# rpi.net
KiCad netlist of a schematic drawn in EAGLE
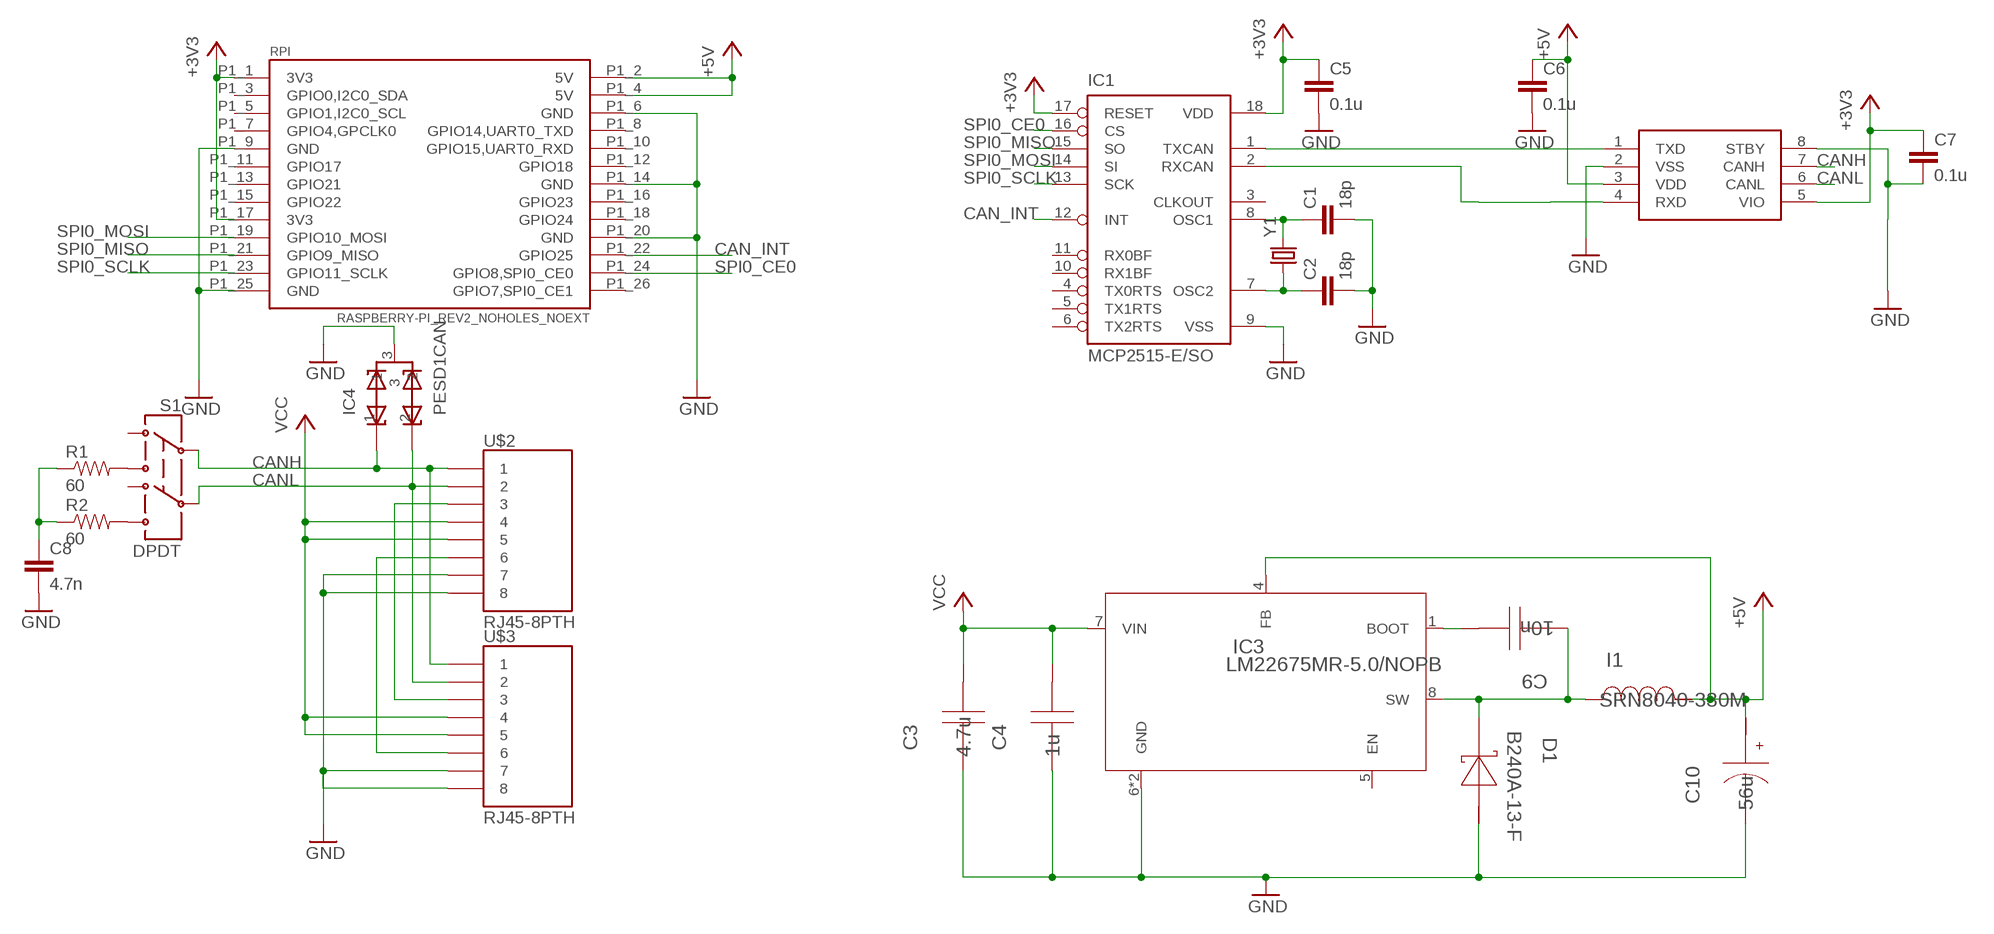
[diagram p0: schematic, sheet 1]

(export (version "E")
  (design (tool "Eeschema 10.0.6"))
  (components
    (comp (ref "C1")
      (value "18p")
      (footprint "eagle-import:0603-CAP")
      (libsource (lib "eagle-import") (part "CAP0603-CAP"))
    )
    (comp (ref "C2")
      (value "18p")
      (footprint "eagle-import:0603-CAP")
      (libsource (lib "eagle-import") (part "CAP0603-CAP"))
    )
    (comp (ref "C3")
      (value "4.7u")
      (footprint "eagle-import:1206")
      (fields (field (name "MANUFACTURER_PART_NUMBER") "GRM31CR71H475KA12L"))
      (libsource (lib "eagle-import") (part "GRM31CR71H475KA12L"))
    )
    (comp (ref "C4")
      (value "1u")
      (footprint "eagle-import:0805")
      (fields (field (name "MANUFACTURER_PART_NUMBER") "GMK212B7105KG-T"))
      (libsource (lib "eagle-import") (part "GMK212B7105KG-T"))
    )
    (comp (ref "C5")
      (value "0.1u")
      (footprint "eagle-import:0603-CAP")
      (libsource (lib "eagle-import") (part "SparkFun-Passives_CAP0603-CAP"))
    )
    (comp (ref "C6")
      (value "0.1u")
      (footprint "eagle-import:0603-CAP")
      (libsource (lib "eagle-import") (part "SparkFun-Passives_CAP0603-CAP"))
    )
    (comp (ref "C7")
      (value "0.1u")
      (footprint "eagle-import:0603-CAP")
      (libsource (lib "eagle-import") (part "SparkFun-Passives_CAP0603-CAP"))
    )
    (comp (ref "C8")
      (value "4.7n")
      (footprint "eagle-import:0603-CAP")
      (libsource (lib "eagle-import") (part "SparkFun-Passives_CAP0603-CAP"))
    )
    (comp (ref "C9")
      (value "10n")
      (footprint "eagle-import:0805")
      (fields (field (name "MANUFACTURER_PART_NUMBER") "C0805C103K5RACTU"))
      (libsource (lib "eagle-import") (part "C0805C103K5RACTU"))
    )
    (comp (ref "C10")
      (value "56u")
      (footprint "eagle-import:SM_RADIAL_6.3AMM")
      (fields (field (name "MANUFACTURER_PART_NUMBER") "10SVP56M"))
      (libsource (lib "eagle-import") (part "10SVP56M"))
    )
    (comp (ref "D1")
      (value "B240A-13-F")
      (footprint "eagle-import:SMA")
      (libsource (lib "eagle-import") (part "B240A-13-F"))
    )
    (comp (ref "I1")
      (value "SRN8040-330M")
      (footprint "eagle-import:SRN8040")
      (libsource (lib "eagle-import") (part "SRN8040-330M"))
    )
    (comp (ref "IC1")
      (value "MCP2515-E/SO")
      (footprint "eagle-import:SO18L")
      (libsource (lib "eagle-import") (part "MCP2515-E/SO"))
    )
    (comp (ref "IC2")
      (value "MCP2562")
      (footprint "eagle-import:SO08")
      (libsource (lib "eagle-import") (part "MCP2562"))
    )
    (comp (ref "IC3")
      (value "LM22675MR-5.0/NOPB")
      (footprint "eagle-import:MRA08B")
      (libsource (lib "eagle-import") (part "LM22675MR-5.0/NOPB"))
    )
    (comp (ref "IC4")
      (value "PESD1CAN")
      (footprint "eagle-import:SOT23")
      (libsource (lib "eagle-import") (part "PESD1CAN"))
    )
    (comp (ref "R1")
      (value "60")
      (footprint "eagle-import:0603-RES")
      (libsource (lib "eagle-import") (part "RESISTOR0603-RES"))
    )
    (comp (ref "R2")
      (value "60")
      (footprint "eagle-import:0603-RES")
      (libsource (lib "eagle-import") (part "RESISTOR0603-RES"))
    )
    (comp (ref "RPI")
      (value "RASPBERRY-PI_REV2_NOHOLES_NOEXT")
      (footprint "eagle-import:RASPBERRY-PI_REV2_NOHOLES_NOEXT")
      (libsource (lib "eagle-import") (part "RASPBERRY-PI_REV2_NOHOLES_NOEXT"))
    )
    (comp (ref "S1")
      (value "DPDT")
      (footprint "eagle-import:AYZ0202")
      (libsource (lib "eagle-import") (part "SWITCH-DPDTAYZ0202"))
    )
    (comp (ref "U$2")
      (value "RJ45-8PTH")
      (footprint "eagle-import:RJ45-8")
      (libsource (lib "eagle-import") (part "RJ45-8PTH"))
    )
    (comp (ref "U$3")
      (value "RJ45-8PTH")
      (footprint "eagle-import:RJ45-8")
      (libsource (lib "eagle-import") (part "RJ45-8PTH"))
    )
    (comp (ref "Y1")
      (value "CRYSTAL5X3")
      (footprint "eagle-import:CRYSTAL-SMD-5X3")
      (libsource (lib "eagle-import") (part "CRYSTAL5X3"))
    )
  )
  (nets
    (net (code "1") (name "+3V3") (class "Default")
      (node (ref "C5") (pin "1") (pinfunction "1_1") (pintype "passive"))
      (node (ref "C7") (pin "1") (pinfunction "1_1") (pintype "passive"))
      (node (ref "IC1") (pin "17") (pinfunction "RESET_17") (pintype "input"))
      (node (ref "IC1") (pin "18") (pinfunction "VDD_18") (pintype "power_in"))
      (node (ref "IC2") (pin "5") (pinfunction "VIO_5") (pintype "bidirectional"))
      (node (ref "RPI") (pin "P1_1") (pinfunction "3V3_P1_1") (pintype "bidirectional"))
      (node (ref "RPI") (pin "P1_17") (pinfunction "3V3_P1_17") (pintype "bidirectional"))
    )
    (net (code "2") (name "+5V") (class "Default")
      (node (ref "C10") (pin "1") (pinfunction "+_1") (pintype "passive"))
      (node (ref "C6") (pin "1") (pinfunction "1_1") (pintype "passive"))
      (node (ref "I1") (pin "1") (pinfunction "1_1") (pintype "passive"))
      (node (ref "IC2") (pin "3") (pinfunction "VDD_3") (pintype "bidirectional"))
      (node (ref "IC3") (pin "4") (pinfunction "FB_4") (pintype "passive"))
      (node (ref "RPI") (pin "P1_2") (pinfunction "5V_P1_2") (pintype "bidirectional"))
      (node (ref "RPI") (pin "P1_4") (pinfunction "5V_P1_4") (pintype "bidirectional"))
    )
    (net (code "3") (name "/CANH") (class "Default")
      (node (ref "IC2") (pin "7") (pinfunction "CANH_7") (pintype "bidirectional"))
      (node (ref "IC4") (pin "1") (pinfunction "1_1") (pintype "bidirectional"))
      (node (ref "S1") (pin "2") (pinfunction "2_2") (pintype "bidirectional"))
      (node (ref "U$2") (pin "1") (pinfunction "1_1") (pintype "bidirectional"))
      (node (ref "U$3") (pin "1") (pinfunction "1_1") (pintype "bidirectional"))
    )
    (net (code "4") (name "/CANL") (class "Default")
      (node (ref "IC2") (pin "6") (pinfunction "CANL_6") (pintype "bidirectional"))
      (node (ref "IC4") (pin "2") (pinfunction "2_2") (pintype "bidirectional"))
      (node (ref "S1") (pin "5") (pinfunction "5_5") (pintype "bidirectional"))
      (node (ref "U$2") (pin "2") (pinfunction "2_2") (pintype "bidirectional"))
      (node (ref "U$3") (pin "2") (pinfunction "2_2") (pintype "bidirectional"))
    )
    (net (code "5") (name "/CAN_INT") (class "Default")
      (node (ref "IC1") (pin "12") (pinfunction "INT_12") (pintype "output"))
      (node (ref "RPI") (pin "P1_22") (pinfunction "GPIO25_P1_22") (pintype "bidirectional"))
    )
    (net (code "6") (name "/SPI0_CE0") (class "Default")
      (node (ref "IC1") (pin "16") (pinfunction "CS_16") (pintype "input"))
      (node (ref "RPI") (pin "P1_24") (pinfunction "GPIO8,SPI0_CE0_P1_24") (pintype "bidirectional"))
    )
    (net (code "7") (name "/SPI0_MISO") (class "Default")
      (node (ref "IC1") (pin "15") (pinfunction "SO_15") (pintype "output"))
      (node (ref "RPI") (pin "P1_21") (pinfunction "GPIO9_MISO_P1_21") (pintype "bidirectional"))
    )
    (net (code "8") (name "/SPI0_MOSI") (class "Default")
      (node (ref "IC1") (pin "14") (pinfunction "SI_14") (pintype "input"))
      (node (ref "RPI") (pin "P1_19") (pinfunction "GPIO10_MOSI_P1_19") (pintype "bidirectional"))
    )
    (net (code "9") (name "/SPI0_SCLK") (class "Default")
      (node (ref "IC1") (pin "13") (pinfunction "SCK_13") (pintype "input"))
      (node (ref "RPI") (pin "P1_23") (pinfunction "GPIO11_SCLK_P1_23") (pintype "bidirectional"))
    )
    (net (code "10") (name "GND") (class "Default")
      (node (ref "C1") (pin "2") (pinfunction "2_2") (pintype "passive"))
      (node (ref "C10") (pin "2") (pinfunction "-_2") (pintype "passive"))
      (node (ref "C2") (pin "2") (pinfunction "2_2") (pintype "passive"))
      (node (ref "C3") (pin "2") (pinfunction "2_2") (pintype "passive"))
      (node (ref "C4") (pin "2") (pinfunction "2_2") (pintype "passive"))
      (node (ref "C5") (pin "2") (pinfunction "2_2") (pintype "passive"))
      (node (ref "C6") (pin "2") (pinfunction "2_2") (pintype "passive"))
      (node (ref "C7") (pin "2") (pinfunction "2_2") (pintype "passive"))
      (node (ref "C8") (pin "2") (pinfunction "2_2") (pintype "passive"))
      (node (ref "D1") (pin "2") (pinfunction "A_2") (pintype "passive"))
      (node (ref "IC1") (pin "9") (pinfunction "VSS_9") (pintype "power_in"))
      (node (ref "IC2") (pin "2") (pinfunction "VSS_2") (pintype "bidirectional"))
      (node (ref "IC2") (pin "8") (pinfunction "STBY_8") (pintype "bidirectional"))
      (node (ref "IC3") (pin "6") (pinfunction "GND_6") (pintype "passive"))
      (node (ref "IC3") (pin "EPAD") (pinfunction "GND_EPAD") (pintype "passive"))
      (node (ref "IC4") (pin "3") (pinfunction "3_3") (pintype "bidirectional"))
      (node (ref "RPI") (pin "P1_14") (pinfunction "GND_P1_14") (pintype "bidirectional"))
      (node (ref "RPI") (pin "P1_20") (pinfunction "GND_P1_20") (pintype "bidirectional"))
      (node (ref "RPI") (pin "P1_25") (pinfunction "GND_P1_25") (pintype "bidirectional"))
      (node (ref "RPI") (pin "P1_6") (pinfunction "GND_P1_6") (pintype "bidirectional"))
      (node (ref "RPI") (pin "P1_9") (pinfunction "GND_P1_9") (pintype "bidirectional"))
      (node (ref "U$2") (pin "7") (pinfunction "7_7") (pintype "bidirectional"))
      (node (ref "U$2") (pin "8") (pinfunction "8_8") (pintype "bidirectional"))
      (node (ref "U$3") (pin "7") (pinfunction "7_7") (pintype "bidirectional"))
      (node (ref "U$3") (pin "8") (pinfunction "8_8") (pintype "bidirectional"))
    )
    (net (code "11") (name "Net-(C8-Pad1)") (class "Default")
      (node (ref "C8") (pin "1") (pinfunction "1_1") (pintype "passive"))
      (node (ref "R1") (pin "1") (pinfunction "1_1") (pintype "passive"))
      (node (ref "R2") (pin "1") (pinfunction "1_1") (pintype "passive"))
    )
    (net (code "12") (name "Net-(D1-K)") (class "Default")
      (node (ref "C9") (pin "2") (pinfunction "2_2") (pintype "passive"))
      (node (ref "D1") (pin "1") (pinfunction "K_1") (pintype "passive"))
      (node (ref "I1") (pin "2") (pinfunction "2_2") (pintype "passive"))
      (node (ref "IC3") (pin "8") (pinfunction "SW_8") (pintype "passive"))
    )
    (net (code "13") (name "Net-(IC1-OSC1)") (class "Default")
      (node (ref "C1") (pin "1") (pinfunction "1_1") (pintype "passive"))
      (node (ref "IC1") (pin "8") (pinfunction "OSC1_8") (pintype "input"))
      (node (ref "Y1") (pin "3") (pinfunction "2_3") (pintype "passive"))
    )
    (net (code "14") (name "Net-(IC1-OSC2)") (class "Default")
      (node (ref "C2") (pin "1") (pinfunction "1_1") (pintype "passive"))
      (node (ref "IC1") (pin "7") (pinfunction "OSC2_7") (pintype "output"))
      (node (ref "Y1") (pin "1") (pinfunction "1_1") (pintype "passive"))
    )
    (net (code "15") (name "Net-(IC1-RXCAN)") (class "Default")
      (node (ref "IC1") (pin "2") (pinfunction "RXCAN_2") (pintype "input"))
      (node (ref "IC2") (pin "4") (pinfunction "RXD_4") (pintype "bidirectional"))
    )
    (net (code "16") (name "Net-(IC1-TXCAN)") (class "Default")
      (node (ref "IC1") (pin "1") (pinfunction "TXCAN_1") (pintype "output"))
      (node (ref "IC2") (pin "1") (pinfunction "TXD_1") (pintype "bidirectional"))
    )
    (net (code "17") (name "Net-(IC3-BOOT)") (class "Default")
      (node (ref "C9") (pin "1") (pinfunction "1_1") (pintype "passive"))
      (node (ref "IC3") (pin "1") (pinfunction "BOOT_1") (pintype "passive"))
    )
    (net (code "18") (name "Net-(R1-Pad2)") (class "Default")
      (node (ref "R1") (pin "2") (pinfunction "2_2") (pintype "passive"))
      (node (ref "S1") (pin "3") (pinfunction "3_3") (pintype "bidirectional"))
    )
    (net (code "19") (name "Net-(R2-Pad2)") (class "Default")
      (node (ref "R2") (pin "2") (pinfunction "2_2") (pintype "passive"))
      (node (ref "S1") (pin "6") (pinfunction "6_6") (pintype "bidirectional"))
    )
    (net (code "20") (name "Net-(U$2-Pad3)") (class "Default")
      (node (ref "U$2") (pin "3") (pinfunction "3_3") (pintype "bidirectional"))
      (node (ref "U$3") (pin "3") (pinfunction "3_3") (pintype "bidirectional"))
    )
    (net (code "21") (name "Net-(U$2-Pad6)") (class "Default")
      (node (ref "U$2") (pin "6") (pinfunction "6_6") (pintype "bidirectional"))
      (node (ref "U$3") (pin "6") (pinfunction "6_6") (pintype "bidirectional"))
    )
    (net (code "22") (name "VCC") (class "Default")
      (node (ref "C3") (pin "1") (pinfunction "1_1") (pintype "passive"))
      (node (ref "C4") (pin "1") (pinfunction "1_1") (pintype "passive"))
      (node (ref "IC3") (pin "7") (pinfunction "VIN_7") (pintype "passive"))
      (node (ref "U$2") (pin "4") (pinfunction "4_4") (pintype "bidirectional"))
      (node (ref "U$2") (pin "5") (pinfunction "5_5") (pintype "bidirectional"))
      (node (ref "U$3") (pin "4") (pinfunction "4_4") (pintype "bidirectional"))
      (node (ref "U$3") (pin "5") (pinfunction "5_5") (pintype "bidirectional"))
    )
    (net (code "23") (name "unconnected-(IC1-CLKOUT-Pad3)") (class "Default")
      (node (ref "IC1") (pin "3") (pinfunction "CLKOUT_3") (pintype "output"))
    )
    (net (code "24") (name "unconnected-(IC1-RX0BF-Pad11)") (class "Default")
      (node (ref "IC1") (pin "11") (pinfunction "RX0BF_11") (pintype "output"))
    )
    (net (code "25") (name "unconnected-(IC1-RX1BF-Pad10)") (class "Default")
      (node (ref "IC1") (pin "10") (pinfunction "RX1BF_10") (pintype "output"))
    )
    (net (code "26") (name "unconnected-(IC1-TX0RTS-Pad4)") (class "Default")
      (node (ref "IC1") (pin "4") (pinfunction "TX0RTS_4") (pintype "input"))
    )
    (net (code "27") (name "unconnected-(IC1-TX1RTS-Pad5)") (class "Default")
      (node (ref "IC1") (pin "5") (pinfunction "TX1RTS_5") (pintype "input"))
    )
    (net (code "28") (name "unconnected-(IC1-TX2RTS-Pad6)") (class "Default")
      (node (ref "IC1") (pin "6") (pinfunction "TX2RTS_6") (pintype "input"))
    )
    (net (code "29") (name "unconnected-(IC3-EN-Pad5)") (class "Default")
      (node (ref "IC3") (pin "5") (pinfunction "EN_5") (pintype "passive"))
    )
    (net (code "30") (name "unconnected-(RPI-GPIO0,I2C0_SDA-PadP1_3)") (class "Default")
      (node (ref "RPI") (pin "P1_3") (pinfunction "GPIO0,I2C0_SDA_P1_3") (pintype "bidirectional"))
    )
    (net (code "31") (name "unconnected-(RPI-GPIO1,I2C0_SCL-PadP1_5)") (class "Default")
      (node (ref "RPI") (pin "P1_5") (pinfunction "GPIO1,I2C0_SCL_P1_5") (pintype "bidirectional"))
    )
    (net (code "32") (name "unconnected-(RPI-GPIO4,GPCLK0-PadP1_7)") (class "Default")
      (node (ref "RPI") (pin "P1_7") (pinfunction "GPIO4,GPCLK0_P1_7") (pintype "bidirectional"))
    )
    (net (code "33") (name "unconnected-(RPI-GPIO7,SPI0_CE1-PadP1_26)") (class "Default")
      (node (ref "RPI") (pin "P1_26") (pinfunction "GPIO7,SPI0_CE1_P1_26") (pintype "bidirectional"))
    )
    (net (code "34") (name "unconnected-(RPI-GPIO14,UART0_TXD-PadP1_8)") (class "Default")
      (node (ref "RPI") (pin "P1_8") (pinfunction "GPIO14,UART0_TXD_P1_8") (pintype "bidirectional"))
    )
    (net (code "35") (name "unconnected-(RPI-GPIO15,UART0_RXD-PadP1_10)") (class "Default")
      (node (ref "RPI") (pin "P1_10") (pinfunction "GPIO15,UART0_RXD_P1_10") (pintype "bidirectional"))
    )
    (net (code "36") (name "unconnected-(RPI-GPIO17-PadP1_11)") (class "Default")
      (node (ref "RPI") (pin "P1_11") (pinfunction "GPIO17_P1_11") (pintype "bidirectional"))
    )
    (net (code "37") (name "unconnected-(RPI-GPIO18-PadP1_12)") (class "Default")
      (node (ref "RPI") (pin "P1_12") (pinfunction "GPIO18_P1_12") (pintype "bidirectional"))
    )
    (net (code "38") (name "unconnected-(RPI-GPIO21-PadP1_13)") (class "Default")
      (node (ref "RPI") (pin "P1_13") (pinfunction "GPIO21_P1_13") (pintype "bidirectional"))
    )
    (net (code "39") (name "unconnected-(RPI-GPIO22-PadP1_15)") (class "Default")
      (node (ref "RPI") (pin "P1_15") (pinfunction "GPIO22_P1_15") (pintype "bidirectional"))
    )
    (net (code "40") (name "unconnected-(RPI-GPIO23-PadP1_16)") (class "Default")
      (node (ref "RPI") (pin "P1_16") (pinfunction "GPIO23_P1_16") (pintype "bidirectional"))
    )
    (net (code "41") (name "unconnected-(RPI-GPIO24-PadP1_18)") (class "Default")
      (node (ref "RPI") (pin "P1_18") (pinfunction "GPIO24_P1_18") (pintype "bidirectional"))
    )
    (net (code "42") (name "unconnected-(S1-Pad1)") (class "Default")
      (node (ref "S1") (pin "1") (pinfunction "1_1") (pintype "bidirectional"))
    )
    (net (code "43") (name "unconnected-(S1-Pad4)") (class "Default")
      (node (ref "S1") (pin "4") (pinfunction "4_4") (pintype "bidirectional"))
    )
  )
)
